# aq_mx_v1-6-0b.net
KiCad netlist of a schematic drawn in EAGLE
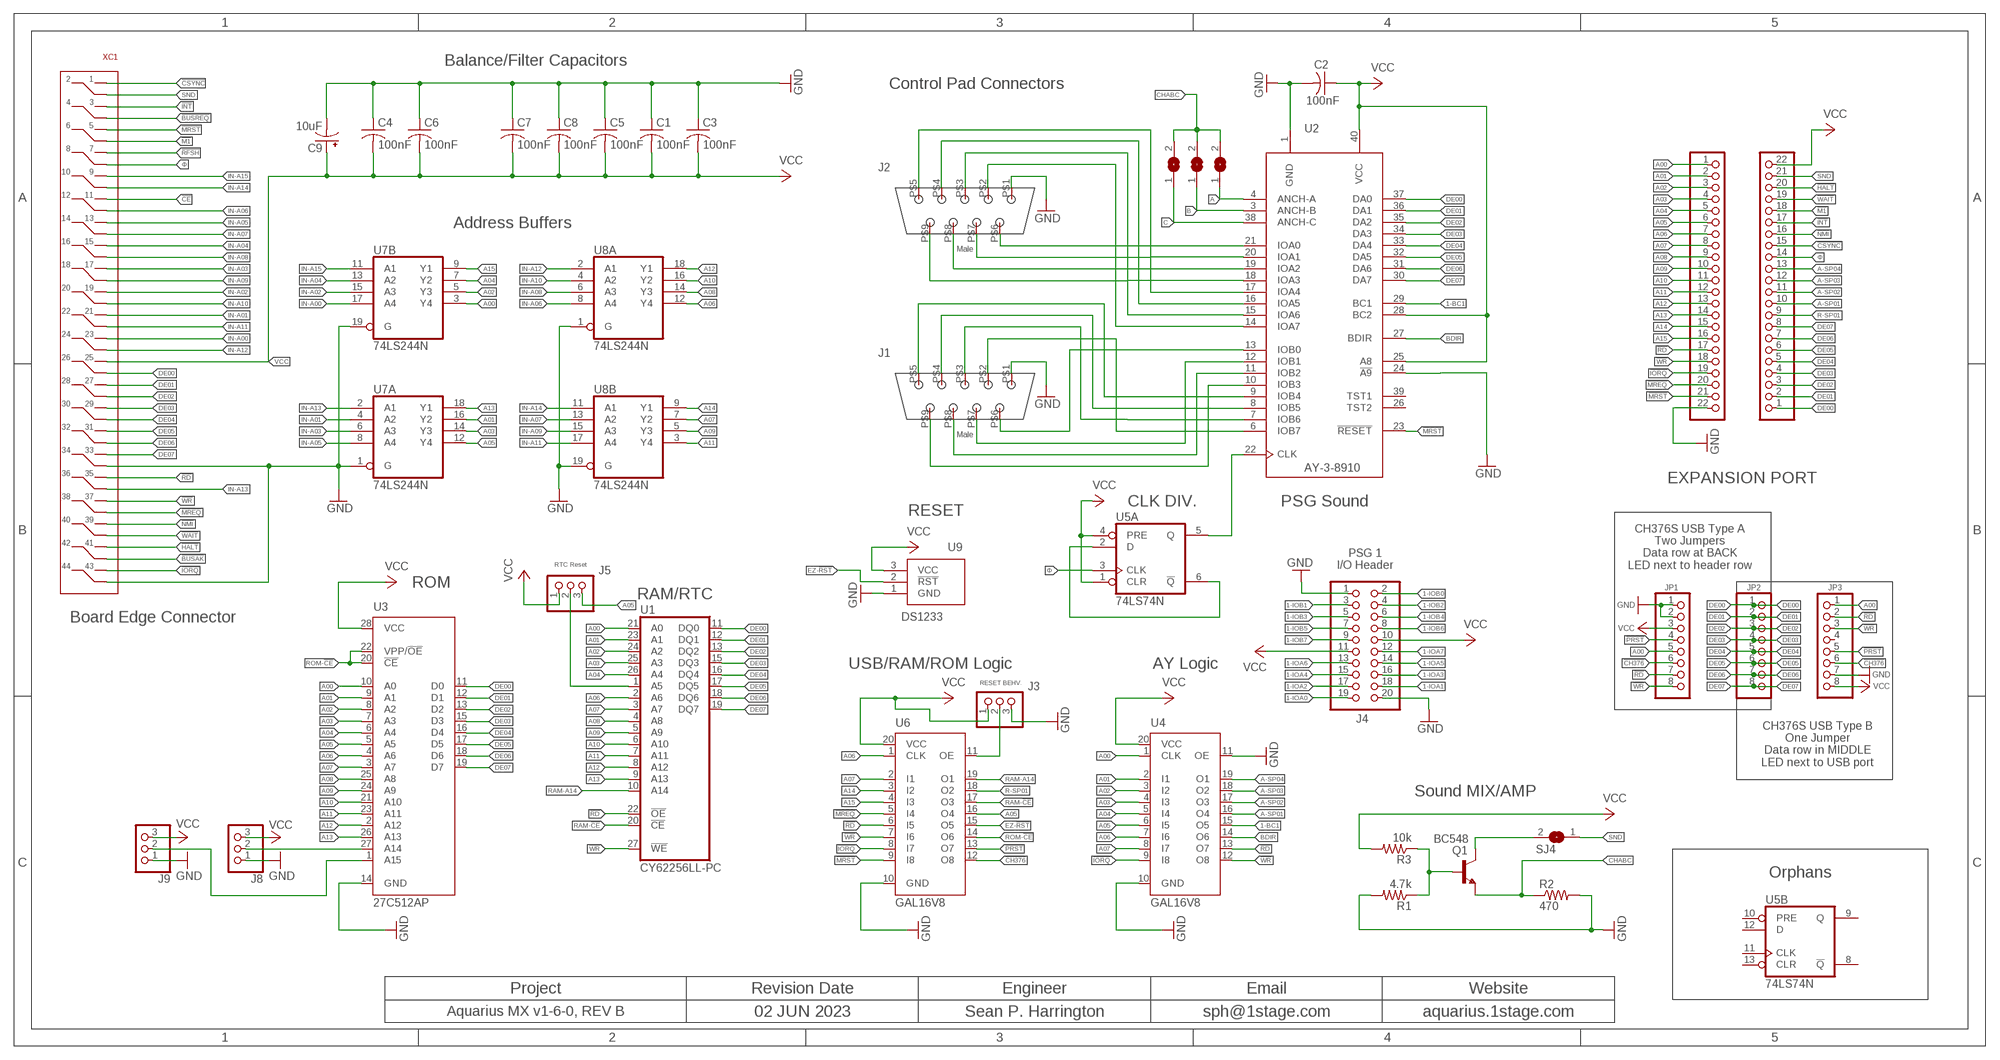
[diagram p0: schematic, sheet 1]

(export (version "E")
  (design (tool "Eeschema 10.0.6"))
  (components
    (comp (ref "C1")
      (value "100nF")
      (footprint "eagle-import:C050-025X075")
      (libsource (lib "eagle-import") (part "C-US050-025X075"))
    )
    (comp (ref "C2")
      (value "100nF")
      (footprint "eagle-import:C050-025X075")
      (libsource (lib "eagle-import") (part "C-US050-025X075"))
    )
    (comp (ref "C3")
      (value "100nF")
      (footprint "eagle-import:C050-025X075")
      (libsource (lib "eagle-import") (part "C-US050-025X075"))
    )
    (comp (ref "C4")
      (value "100nF")
      (footprint "eagle-import:C050-025X075")
      (libsource (lib "eagle-import") (part "C-US050-025X075"))
    )
    (comp (ref "C5")
      (value "100nF")
      (footprint "eagle-import:C050-025X075")
      (libsource (lib "eagle-import") (part "C-US050-025X075"))
    )
    (comp (ref "C6")
      (value "100nF")
      (footprint "eagle-import:C050-025X075")
      (libsource (lib "eagle-import") (part "C-US050-025X075"))
    )
    (comp (ref "C7")
      (value "100nF")
      (footprint "eagle-import:C050-025X075")
      (libsource (lib "eagle-import") (part "C-US050-025X075"))
    )
    (comp (ref "C8")
      (value "100nF")
      (footprint "eagle-import:C050-025X075")
      (libsource (lib "eagle-import") (part "C-US050-025X075"))
    )
    (comp (ref "C9")
      (value "10uF")
      (footprint "eagle-import:E22-6")
      (libsource (lib "eagle-import") (part "CPOL-USE22-6AXIAL"))
    )
    (comp (ref "J1")
      (value "DB9-MALE-RA")
      (footprint "eagle-import:DB9-MALE-RA")
      (libsource (lib "eagle-import") (part "DB9-MALE-RA"))
    )
    (comp (ref "J2")
      (value "DB9-MALE-RA")
      (footprint "eagle-import:DB9-MALE-RA")
      (libsource (lib "eagle-import") (part "DB9-MALE-RA"))
    )
    (comp (ref "J3")
      (value "RESET BEHV.")
      (footprint "eagle-import:1X03")
      (libsource (lib "eagle-import") (part "PINHD-1X3"))
    )
    (comp (ref "J4")
      (value "PINHD-2X10")
      (footprint "eagle-import:2X10")
      (libsource (lib "eagle-import") (part "PINHD-2X10"))
    )
    (comp (ref "J5")
      (value "RTC Reset")
      (footprint "eagle-import:1X03")
      (libsource (lib "eagle-import") (part "PINHD-1X3"))
    )
    (comp (ref "J6")
      (value "PINHD-1X22")
      (footprint "eagle-import:1X22")
      (libsource (lib "eagle-import") (part "PINHD-1X22"))
    )
    (comp (ref "J7")
      (value "PINHD-1X22")
      (footprint "eagle-import:1X22")
      (libsource (lib "eagle-import") (part "PINHD-1X22"))
    )
    (comp (ref "J8")
      (value "PINHD-1X3")
      (footprint "eagle-import:1X03")
      (libsource (lib "eagle-import") (part "PINHD-1X3"))
    )
    (comp (ref "J9")
      (value "PINHD-1X3")
      (footprint "eagle-import:1X03")
      (libsource (lib "eagle-import") (part "PINHD-1X3"))
    )
    (comp (ref "JP1")
      (value "PINHD-1X8")
      (footprint "eagle-import:1X08")
      (libsource (lib "eagle-import") (part "PINHD-1X8"))
    )
    (comp (ref "JP2")
      (value "PINHD-1X8")
      (footprint "eagle-import:1X08")
      (libsource (lib "eagle-import") (part "PINHD-1X8"))
    )
    (comp (ref "JP3")
      (value "PINHD-1X8")
      (footprint "eagle-import:1X08")
      (libsource (lib "eagle-import") (part "PINHD-1X8"))
    )
    (comp (ref "Q1")
      (value "BC548")
      (footprint "eagle-import:TO92-CBE")
      (libsource (lib "eagle-import") (part "-NPN-TO92-CBEBC548"))
    )
    (comp (ref "R1")
      (value "4.7k")
      (footprint "eagle-import:0204_7")
      (libsource (lib "eagle-import") (part "R-US_0204/7"))
    )
    (comp (ref "R2")
      (value "470")
      (footprint "eagle-import:0204_7")
      (libsource (lib "eagle-import") (part "R-US_0204/7"))
    )
    (comp (ref "R3")
      (value "10k")
      (footprint "eagle-import:0204_7")
      (libsource (lib "eagle-import") (part "R-US_0204/7"))
    )
    (comp (ref "SJ1") (value "SJ") (footprint "eagle-import:SJ") (libsource (lib "eagle-import") (part "SJ")))
    (comp (ref "SJ2") (value "SJ") (footprint "eagle-import:SJ") (libsource (lib "eagle-import") (part "SJ")))
    (comp (ref "SJ3") (value "SJ") (footprint "eagle-import:SJ") (libsource (lib "eagle-import") (part "SJ")))
    (comp (ref "SJ4") (value "SJ") (footprint "eagle-import:SJ") (libsource (lib "eagle-import") (part "SJ")))
    (comp (ref "U1")
      (value "CY62256LL-PC")
      (footprint "eagle-import:DIL28-6")
      (libsource (lib "eagle-import") (part "CY62256LL-?PC"))
    )
    (comp (ref "U2")
      (value "AY-3-8910")
      (footprint "eagle-import:RAD38910-DIL40-6")
      (libsource (lib "eagle-import") (part "RAD38910DIL40-6"))
    )
    (comp (ref "U3")
      (value "27C512AP")
      (footprint "eagle-import:DIL28-6")
      (fields (field (name "MPN") "M27C512-90B6"))
      (libsource (lib "eagle-import") (part "27512APC"))
    )
    (comp (ref "U4")
      (value "GAL16V8")
      (footprint "eagle-import:DIL20")
      (fields (field (name "MPN") "ATF16V8CZ-15PU"))
      (libsource (lib "eagle-import") (part "ATF16V8BP3"))
    )
    (comp (ref "U5")
      (value "74LS74N")
      (footprint "eagle-import:DIL14")
      (libsource (lib "eagle-import") (part "7474NLS"))
    )
    (comp (ref "U6")
      (value "GAL16V8")
      (footprint "eagle-import:DIL20")
      (fields (field (name "MPN") "ATF16V8CZ-15PU"))
      (libsource (lib "eagle-import") (part "ATF16V8BP3"))
    )
    (comp (ref "U7")
      (value "74LS244N")
      (footprint "eagle-import:DIL20")
      (libsource (lib "eagle-import") (part "74244NLS"))
    )
    (comp (ref "U8")
      (value "74LS244N")
      (footprint "eagle-import:DIL20")
      (libsource (lib "eagle-import") (part "74244NLS"))
    )
    (comp (ref "U9")
      (value "DS1233")
      (footprint "eagle-import:TO-92")
      (fields
        (field (name "ARROW_PART_NUMBER") "DS1233-10+")
        (field (name "MOUSER_PART_NUMBER") "700-DS1233-10")
      )
      (libsource (lib "eagle-import") (part "DS1233-10+"))
    )
    (comp (ref "XC1")
      (value "AQ-CART-EDGE")
      (footprint "eagle-import:AQ-CART-EDGE")
      (libsource (lib "eagle-import") (part "AQ-CART-EDGE"))
    )
  )
  (nets
    (net (code "1") (name "/EZ-~{RST}") (class "Default")
      (node (ref "U6") (pin "15") (pinfunction "O5_15") (pintype "output"))
      (node (ref "U9") (pin "2") (pinfunction "~{RST}_2") (pintype "input"))
    )
    (net (code "2") (name "/RAM-~{CE}") (class "Default")
      (node (ref "U1") (pin "20") (pinfunction "~{CE}_20") (pintype "input"))
      (node (ref "U6") (pin "17") (pinfunction "O3_17") (pintype "output"))
    )
    (net (code "3") (name "/ROM-~{CE}") (class "Default")
      (node (ref "U3") (pin "20") (pinfunction "~{CE}_20") (pintype "input"))
      (node (ref "U3") (pin "22") (pinfunction "VPP/~{OE}_22") (pintype "input"))
      (node (ref "U6") (pin "14") (pinfunction "O6_14") (pintype "output"))
    )
    (net (code "4") (name "/~{BUSAK}") (class "Default")
      (node (ref "XC1") (pin "P$42") (pinfunction "X42_P$42") (pintype "bidirectional"))
    )
    (net (code "5") (name "/~{BUSREQ}") (class "Default")
      (node (ref "XC1") (pin "P$4") (pinfunction "X4_P$4") (pintype "bidirectional"))
    )
    (net (code "6") (name "/~{CE}") (class "Default")
      (node (ref "XC1") (pin "P$11") (pinfunction "X11_P$11") (pintype "bidirectional"))
    )
    (net (code "7") (name "/~{CH376}") (class "Default")
      (node (ref "JP1") (pin "6") (pinfunction "6_6") (pintype "passive"))
      (node (ref "JP3") (pin "6") (pinfunction "6_6") (pintype "passive"))
      (node (ref "U6") (pin "12") (pinfunction "O8_12") (pintype "output"))
    )
    (net (code "8") (name "/~{CSYNC}") (class "Default")
      (node (ref "J6") (pin "15") (pinfunction "15_15") (pintype "passive"))
      (node (ref "XC1") (pin "P$1") (pinfunction "X1_P$1") (pintype "bidirectional"))
    )
    (net (code "9") (name "/~{HALT}") (class "Default")
      (node (ref "J6") (pin "20") (pinfunction "20_20") (pintype "passive"))
      (node (ref "XC1") (pin "P$41") (pinfunction "X41_P$41") (pintype "bidirectional"))
    )
    (net (code "10") (name "/~{INT}") (class "Default")
      (node (ref "J6") (pin "17") (pinfunction "17_17") (pintype "passive"))
      (node (ref "XC1") (pin "P$3") (pinfunction "X3_P$3") (pintype "bidirectional"))
    )
    (net (code "11") (name "/~{IORQ}") (class "Default")
      (node (ref "J7") (pin "19") (pinfunction "19_19") (pintype "passive"))
      (node (ref "U4") (pin "9") (pinfunction "I8_9") (pintype "input"))
      (node (ref "U6") (pin "8") (pinfunction "I7_8") (pintype "input"))
      (node (ref "XC1") (pin "P$43") (pinfunction "X43_P$43") (pintype "bidirectional"))
    )
    (net (code "12") (name "/~{M1}") (class "Default")
      (node (ref "J6") (pin "18") (pinfunction "18_18") (pintype "passive"))
      (node (ref "XC1") (pin "P$6") (pinfunction "X6_P$6") (pintype "bidirectional"))
    )
    (net (code "13") (name "/~{MREQ}") (class "Default")
      (node (ref "J7") (pin "20") (pinfunction "20_20") (pintype "passive"))
      (node (ref "U6") (pin "5") (pinfunction "I4_5") (pintype "input"))
      (node (ref "XC1") (pin "P$38") (pinfunction "X38_P$38") (pintype "bidirectional"))
    )
    (net (code "14") (name "/~{MRST}") (class "Default")
      (node (ref "J7") (pin "21") (pinfunction "21_21") (pintype "passive"))
      (node (ref "U2") (pin "23") (pinfunction "~{RESET}_23") (pintype "bidirectional"))
      (node (ref "U6") (pin "9") (pinfunction "I8_9") (pintype "input"))
      (node (ref "XC1") (pin "P$5") (pinfunction "X5_P$5") (pintype "bidirectional"))
    )
    (net (code "15") (name "/~{NMI}") (class "Default")
      (node (ref "J6") (pin "16") (pinfunction "16_16") (pintype "passive"))
      (node (ref "XC1") (pin "P$39") (pinfunction "X39_P$39") (pintype "bidirectional"))
    )
    (net (code "16") (name "/~{PRST}") (class "Default")
      (node (ref "JP1") (pin "4") (pinfunction "4_4") (pintype "passive"))
      (node (ref "JP3") (pin "5") (pinfunction "5_5") (pintype "passive"))
      (node (ref "U6") (pin "13") (pinfunction "O7_13") (pintype "output"))
    )
    (net (code "17") (name "/~{RD}") (class "Default")
      (node (ref "J7") (pin "17") (pinfunction "17_17") (pintype "passive"))
      (node (ref "JP1") (pin "7") (pinfunction "7_7") (pintype "passive"))
      (node (ref "JP3") (pin "2") (pinfunction "2_2") (pintype "passive"))
      (node (ref "U1") (pin "22") (pinfunction "~{OE}_22") (pintype "input"))
      (node (ref "U4") (pin "13") (pinfunction "O7_13") (pintype "output"))
      (node (ref "U6") (pin "6") (pinfunction "I5_6") (pintype "input"))
      (node (ref "XC1") (pin "P$35") (pinfunction "X35_P$35") (pintype "bidirectional"))
    )
    (net (code "18") (name "/~{RFSH}") (class "Default")
      (node (ref "XC1") (pin "P$7") (pinfunction "X7_P$7") (pintype "bidirectional"))
    )
    (net (code "19") (name "/~{WAIT}") (class "Default")
      (node (ref "J6") (pin "19") (pinfunction "19_19") (pintype "passive"))
      (node (ref "XC1") (pin "P$40") (pinfunction "X40_P$40") (pintype "bidirectional"))
    )
    (net (code "20") (name "/~{WR}") (class "Default")
      (node (ref "J7") (pin "18") (pinfunction "18_18") (pintype "passive"))
      (node (ref "JP1") (pin "8") (pinfunction "8_8") (pintype "passive"))
      (node (ref "JP3") (pin "3") (pinfunction "3_3") (pintype "passive"))
      (node (ref "U1") (pin "27") (pinfunction "~{WE}_27") (pintype "input"))
      (node (ref "U4") (pin "12") (pinfunction "O8_12") (pintype "output"))
      (node (ref "U6") (pin "7") (pinfunction "I6_7") (pintype "input"))
      (node (ref "XC1") (pin "P$37") (pinfunction "X37_P$37") (pintype "bidirectional"))
    )
    (net (code "21") (name "1-BC1") (class "Default")
      (node (ref "U2") (pin "29") (pinfunction "BC1_29") (pintype "bidirectional"))
      (node (ref "U4") (pin "15") (pinfunction "O5_15") (pintype "output"))
    )
    (net (code "22") (name "1-IOA0") (class "Default")
      (node (ref "J2") (pin "P$6") (pinfunction "P$6_P$6") (pintype "bidirectional"))
      (node (ref "J4") (pin "19") (pinfunction "19_19") (pintype "passive"))
      (node (ref "U2") (pin "21") (pinfunction "IOA0_21") (pintype "bidirectional"))
    )
    (net (code "23") (name "1-IOA1") (class "Default")
      (node (ref "J2") (pin "P$7") (pinfunction "P$7_P$7") (pintype "bidirectional"))
      (node (ref "J4") (pin "18") (pinfunction "18_18") (pintype "passive"))
      (node (ref "U2") (pin "20") (pinfunction "IOA1_20") (pintype "bidirectional"))
    )
    (net (code "24") (name "1-IOA2") (class "Default")
      (node (ref "J2") (pin "P$8") (pinfunction "P$8_P$8") (pintype "bidirectional"))
      (node (ref "J4") (pin "17") (pinfunction "17_17") (pintype "passive"))
      (node (ref "U2") (pin "19") (pinfunction "IOA2_19") (pintype "bidirectional"))
    )
    (net (code "25") (name "1-IOA3") (class "Default")
      (node (ref "J2") (pin "P$9") (pinfunction "P$9_P$9") (pintype "bidirectional"))
      (node (ref "J4") (pin "16") (pinfunction "16_16") (pintype "passive"))
      (node (ref "U2") (pin "18") (pinfunction "IOA3_18") (pintype "bidirectional"))
    )
    (net (code "26") (name "1-IOA4") (class "Default")
      (node (ref "J2") (pin "P$5") (pinfunction "P$5_P$5") (pintype "bidirectional"))
      (node (ref "J4") (pin "15") (pinfunction "15_15") (pintype "passive"))
      (node (ref "U2") (pin "17") (pinfunction "IOA4_17") (pintype "bidirectional"))
    )
    (net (code "27") (name "1-IOA5") (class "Default")
      (node (ref "J2") (pin "P$4") (pinfunction "P$4_P$4") (pintype "bidirectional"))
      (node (ref "J4") (pin "14") (pinfunction "14_14") (pintype "passive"))
      (node (ref "U2") (pin "16") (pinfunction "IOA5_16") (pintype "bidirectional"))
    )
    (net (code "28") (name "1-IOA6") (class "Default")
      (node (ref "J2") (pin "P$3") (pinfunction "P$3_P$3") (pintype "bidirectional"))
      (node (ref "J4") (pin "13") (pinfunction "13_13") (pintype "passive"))
      (node (ref "U2") (pin "15") (pinfunction "IOA6_15") (pintype "bidirectional"))
    )
    (net (code "29") (name "1-IOA7") (class "Default")
      (node (ref "J2") (pin "P$2") (pinfunction "P$2_P$2") (pintype "bidirectional"))
      (node (ref "J4") (pin "12") (pinfunction "12_12") (pintype "passive"))
      (node (ref "U2") (pin "14") (pinfunction "IOA7_14") (pintype "bidirectional"))
    )
    (net (code "30") (name "1-IOB0") (class "Default")
      (node (ref "J1") (pin "P$6") (pinfunction "P$6_P$6") (pintype "bidirectional"))
      (node (ref "J4") (pin "2") (pinfunction "2_2") (pintype "passive"))
      (node (ref "U2") (pin "13") (pinfunction "IOB0_13") (pintype "bidirectional"))
    )
    (net (code "31") (name "1-IOB1") (class "Default")
      (node (ref "J1") (pin "P$7") (pinfunction "P$7_P$7") (pintype "bidirectional"))
      (node (ref "J4") (pin "3") (pinfunction "3_3") (pintype "passive"))
      (node (ref "U2") (pin "12") (pinfunction "IOB1_12") (pintype "bidirectional"))
    )
    (net (code "32") (name "1-IOB2") (class "Default")
      (node (ref "J1") (pin "P$8") (pinfunction "P$8_P$8") (pintype "bidirectional"))
      (node (ref "J4") (pin "4") (pinfunction "4_4") (pintype "passive"))
      (node (ref "U2") (pin "11") (pinfunction "IOB2_11") (pintype "bidirectional"))
    )
    (net (code "33") (name "1-IOB3") (class "Default")
      (node (ref "J1") (pin "P$9") (pinfunction "P$9_P$9") (pintype "bidirectional"))
      (node (ref "J4") (pin "5") (pinfunction "5_5") (pintype "passive"))
      (node (ref "U2") (pin "10") (pinfunction "IOB3_10") (pintype "bidirectional"))
    )
    (net (code "34") (name "1-IOB4") (class "Default")
      (node (ref "J1") (pin "P$5") (pinfunction "P$5_P$5") (pintype "bidirectional"))
      (node (ref "J4") (pin "6") (pinfunction "6_6") (pintype "passive"))
      (node (ref "U2") (pin "9") (pinfunction "IOB4_9") (pintype "bidirectional"))
    )
    (net (code "35") (name "1-IOB5") (class "Default")
      (node (ref "J1") (pin "P$4") (pinfunction "P$4_P$4") (pintype "bidirectional"))
      (node (ref "J4") (pin "7") (pinfunction "7_7") (pintype "passive"))
      (node (ref "U2") (pin "8") (pinfunction "IOB5_8") (pintype "bidirectional"))
    )
    (net (code "36") (name "1-IOB6") (class "Default")
      (node (ref "J1") (pin "P$3") (pinfunction "P$3_P$3") (pintype "bidirectional"))
      (node (ref "J4") (pin "8") (pinfunction "8_8") (pintype "passive"))
      (node (ref "U2") (pin "7") (pinfunction "IOB6_7") (pintype "bidirectional"))
    )
    (net (code "37") (name "1-IOB7") (class "Default")
      (node (ref "J1") (pin "P$2") (pinfunction "P$2_P$2") (pintype "bidirectional"))
      (node (ref "J4") (pin "9") (pinfunction "9_9") (pintype "passive"))
      (node (ref "U2") (pin "6") (pinfunction "IOB7_6") (pintype "bidirectional"))
    )
    (net (code "38") (name "A") (class "Default")
      (node (ref "SJ1") (pin "1") (pinfunction "1_1") (pintype "passive"))
      (node (ref "U2") (pin "4") (pinfunction "ANCH-A_4") (pintype "bidirectional"))
    )
    (net (code "39") (name "A-SP01") (class "Default")
      (node (ref "J6") (pin "10") (pinfunction "10_10") (pintype "passive"))
      (node (ref "U4") (pin "16") (pinfunction "O4_16") (pintype "output"))
    )
    (net (code "40") (name "A-SP02") (class "Default")
      (node (ref "J6") (pin "11") (pinfunction "11_11") (pintype "passive"))
      (node (ref "U4") (pin "17") (pinfunction "O3_17") (pintype "output"))
    )
    (net (code "41") (name "A-SP03") (class "Default")
      (node (ref "J6") (pin "12") (pinfunction "12_12") (pintype "passive"))
      (node (ref "U4") (pin "18") (pinfunction "O2_18") (pintype "output"))
    )
    (net (code "42") (name "A-SP04") (class "Default")
      (node (ref "J6") (pin "13") (pinfunction "13_13") (pintype "passive"))
      (node (ref "U4") (pin "19") (pinfunction "O1_19") (pintype "output"))
    )
    (net (code "43") (name "A00") (class "Default")
      (node (ref "J7") (pin "1") (pinfunction "1_1") (pintype "passive"))
      (node (ref "JP1") (pin "5") (pinfunction "5_5") (pintype "passive"))
      (node (ref "JP3") (pin "1") (pinfunction "1_1") (pintype "passive"))
      (node (ref "U1") (pin "21") (pinfunction "A0_21") (pintype "input"))
      (node (ref "U3") (pin "10") (pinfunction "A0_10") (pintype "input"))
      (node (ref "U4") (pin "1") (pinfunction "CLK_1") (pintype "input"))
      (node (ref "U7") (pin "3") (pinfunction "Y4_3") (pintype "tri_state"))
    )
    (net (code "44") (name "A01") (class "Default")
      (node (ref "J7") (pin "2") (pinfunction "2_2") (pintype "passive"))
      (node (ref "U1") (pin "23") (pinfunction "A1_23") (pintype "input"))
      (node (ref "U3") (pin "9") (pinfunction "A1_9") (pintype "input"))
      (node (ref "U4") (pin "2") (pinfunction "I1_2") (pintype "input"))
      (node (ref "U7") (pin "16") (pinfunction "Y2_16") (pintype "tri_state"))
    )
    (net (code "45") (name "A02") (class "Default")
      (node (ref "J7") (pin "3") (pinfunction "3_3") (pintype "passive"))
      (node (ref "U1") (pin "24") (pinfunction "A2_24") (pintype "input"))
      (node (ref "U3") (pin "8") (pinfunction "A2_8") (pintype "input"))
      (node (ref "U4") (pin "3") (pinfunction "I2_3") (pintype "input"))
      (node (ref "U7") (pin "5") (pinfunction "Y3_5") (pintype "tri_state"))
    )
    (net (code "46") (name "A03") (class "Default")
      (node (ref "J7") (pin "4") (pinfunction "4_4") (pintype "passive"))
      (node (ref "U1") (pin "25") (pinfunction "A3_25") (pintype "input"))
      (node (ref "U3") (pin "7") (pinfunction "A3_7") (pintype "input"))
      (node (ref "U4") (pin "4") (pinfunction "I3_4") (pintype "input"))
      (node (ref "U7") (pin "14") (pinfunction "Y3_14") (pintype "tri_state"))
    )
    (net (code "47") (name "A04") (class "Default")
      (node (ref "J7") (pin "5") (pinfunction "5_5") (pintype "passive"))
      (node (ref "U1") (pin "26") (pinfunction "A4_26") (pintype "input"))
      (node (ref "U3") (pin "6") (pinfunction "A4_6") (pintype "input"))
      (node (ref "U4") (pin "5") (pinfunction "I4_5") (pintype "input"))
      (node (ref "U7") (pin "7") (pinfunction "Y2_7") (pintype "tri_state"))
    )
    (net (code "48") (name "A05") (class "Default")
      (node (ref "J5") (pin "3") (pinfunction "3_3") (pintype "passive"))
      (node (ref "J7") (pin "6") (pinfunction "6_6") (pintype "passive"))
      (node (ref "U3") (pin "5") (pinfunction "A5_5") (pintype "input"))
      (node (ref "U4") (pin "6") (pinfunction "I5_6") (pintype "input"))
      (node (ref "U6") (pin "16") (pinfunction "O4_16") (pintype "output"))
      (node (ref "U7") (pin "12") (pinfunction "Y4_12") (pintype "tri_state"))
    )
    (net (code "49") (name "A06") (class "Default")
      (node (ref "J7") (pin "7") (pinfunction "7_7") (pintype "passive"))
      (node (ref "U1") (pin "2") (pinfunction "A6_2") (pintype "input"))
      (node (ref "U3") (pin "4") (pinfunction "A6_4") (pintype "input"))
      (node (ref "U4") (pin "7") (pinfunction "I6_7") (pintype "input"))
      (node (ref "U6") (pin "1") (pinfunction "CLK_1") (pintype "input"))
      (node (ref "U8") (pin "12") (pinfunction "Y4_12") (pintype "tri_state"))
    )
    (net (code "50") (name "A07") (class "Default")
      (node (ref "J7") (pin "8") (pinfunction "8_8") (pintype "passive"))
      (node (ref "U1") (pin "3") (pinfunction "A7_3") (pintype "input"))
      (node (ref "U3") (pin "3") (pinfunction "A7_3") (pintype "input"))
      (node (ref "U4") (pin "8") (pinfunction "I7_8") (pintype "input"))
      (node (ref "U6") (pin "2") (pinfunction "I1_2") (pintype "input"))
      (node (ref "U8") (pin "7") (pinfunction "Y2_7") (pintype "tri_state"))
    )
    (net (code "51") (name "A08") (class "Default")
      (node (ref "J7") (pin "9") (pinfunction "9_9") (pintype "passive"))
      (node (ref "U1") (pin "4") (pinfunction "A8_4") (pintype "input"))
      (node (ref "U3") (pin "25") (pinfunction "A8_25") (pintype "input"))
      (node (ref "U8") (pin "14") (pinfunction "Y3_14") (pintype "tri_state"))
    )
    (net (code "52") (name "A09") (class "Default")
      (node (ref "J7") (pin "10") (pinfunction "10_10") (pintype "passive"))
      (node (ref "U1") (pin "5") (pinfunction "A9_5") (pintype "input"))
      (node (ref "U3") (pin "24") (pinfunction "A9_24") (pintype "input"))
      (node (ref "U8") (pin "5") (pinfunction "Y3_5") (pintype "tri_state"))
    )
    (net (code "53") (name "A10") (class "Default")
      (node (ref "J7") (pin "11") (pinfunction "11_11") (pintype "passive"))
      (node (ref "U1") (pin "6") (pinfunction "A10_6") (pintype "input"))
      (node (ref "U3") (pin "21") (pinfunction "A10_21") (pintype "input"))
      (node (ref "U8") (pin "16") (pinfunction "Y2_16") (pintype "tri_state"))
    )
    (net (code "54") (name "A11") (class "Default")
      (node (ref "J7") (pin "12") (pinfunction "12_12") (pintype "passive"))
      (node (ref "U1") (pin "7") (pinfunction "A11_7") (pintype "input"))
      (node (ref "U3") (pin "23") (pinfunction "A11_23") (pintype "input"))
      (node (ref "U8") (pin "3") (pinfunction "Y4_3") (pintype "tri_state"))
    )
    (net (code "55") (name "A12") (class "Default")
      (node (ref "J7") (pin "13") (pinfunction "13_13") (pintype "passive"))
      (node (ref "U1") (pin "8") (pinfunction "A12_8") (pintype "input"))
      (node (ref "U3") (pin "2") (pinfunction "A12_2") (pintype "input"))
      (node (ref "U8") (pin "18") (pinfunction "Y1_18") (pintype "tri_state"))
    )
    (net (code "56") (name "A13") (class "Default")
      (node (ref "J7") (pin "14") (pinfunction "14_14") (pintype "passive"))
      (node (ref "U1") (pin "9") (pinfunction "A13_9") (pintype "input"))
      (node (ref "U3") (pin "26") (pinfunction "A13_26") (pintype "input"))
      (node (ref "U7") (pin "18") (pinfunction "Y1_18") (pintype "tri_state"))
    )
    (net (code "57") (name "A14") (class "Default")
      (node (ref "J7") (pin "15") (pinfunction "15_15") (pintype "passive"))
      (node (ref "U6") (pin "3") (pinfunction "I2_3") (pintype "input"))
      (node (ref "U8") (pin "9") (pinfunction "Y1_9") (pintype "tri_state"))
    )
    (net (code "58") (name "A15") (class "Default")
      (node (ref "J7") (pin "16") (pinfunction "16_16") (pintype "passive"))
      (node (ref "U6") (pin "4") (pinfunction "I3_4") (pintype "input"))
      (node (ref "U7") (pin "9") (pinfunction "Y1_9") (pintype "tri_state"))
    )
    (net (code "59") (name "B") (class "Default")
      (node (ref "SJ2") (pin "1") (pinfunction "1_1") (pintype "passive"))
      (node (ref "U2") (pin "3") (pinfunction "ANCH-B_3") (pintype "bidirectional"))
    )
    (net (code "60") (name "BDIR") (class "Default")
      (node (ref "U2") (pin "27") (pinfunction "BDIR_27") (pintype "bidirectional"))
      (node (ref "U4") (pin "14") (pinfunction "O6_14") (pintype "output"))
    )
    (net (code "61") (name "C") (class "Default")
      (node (ref "SJ3") (pin "1") (pinfunction "1_1") (pintype "passive"))
      (node (ref "U2") (pin "38") (pinfunction "ANCH-C_38") (pintype "bidirectional"))
    )
    (net (code "62") (name "CHABC") (class "Default")
      (node (ref "Q1") (pin "E") (pinfunction "E_E") (pintype "passive"))
      (node (ref "R2") (pin "1") (pinfunction "1_1") (pintype "passive"))
      (node (ref "SJ1") (pin "2") (pinfunction "2_2") (pintype "passive"))
      (node (ref "SJ2") (pin "2") (pinfunction "2_2") (pintype "passive"))
      (node (ref "SJ3") (pin "2") (pinfunction "2_2") (pintype "passive"))
    )
    (net (code "63") (name "DE00") (class "Default")
      (node (ref "J6") (pin "1") (pinfunction "1_1") (pintype "passive"))
      (node (ref "JP2") (pin "1") (pinfunction "1_1") (pintype "passive"))
      (node (ref "U1") (pin "11") (pinfunction "DQ0_11") (pintype "bidirectional"))
      (node (ref "U2") (pin "37") (pinfunction "DA0_37") (pintype "bidirectional"))
      (node (ref "U3") (pin "11") (pinfunction "D0_11") (pintype "tri_state"))
      (node (ref "XC1") (pin "P$26") (pinfunction "X26_P$26") (pintype "bidirectional"))
    )
    (net (code "64") (name "DE01") (class "Default")
      (node (ref "J6") (pin "2") (pinfunction "2_2") (pintype "passive"))
      (node (ref "JP2") (pin "2") (pinfunction "2_2") (pintype "passive"))
      (node (ref "U1") (pin "12") (pinfunction "DQ1_12") (pintype "bidirectional"))
      (node (ref "U2") (pin "36") (pinfunction "DA1_36") (pintype "bidirectional"))
      (node (ref "U3") (pin "12") (pinfunction "D1_12") (pintype "tri_state"))
      (node (ref "XC1") (pin "P$27") (pinfunction "X27_P$27") (pintype "bidirectional"))
    )
    (net (code "65") (name "DE02") (class "Default")
      (node (ref "J6") (pin "3") (pinfunction "3_3") (pintype "passive"))
      (node (ref "JP2") (pin "3") (pinfunction "3_3") (pintype "passive"))
      (node (ref "U1") (pin "13") (pinfunction "DQ2_13") (pintype "bidirectional"))
      (node (ref "U2") (pin "35") (pinfunction "DA2_35") (pintype "bidirectional"))
      (node (ref "U3") (pin "13") (pinfunction "D2_13") (pintype "tri_state"))
      (node (ref "XC1") (pin "P$28") (pinfunction "X28_P$28") (pintype "bidirectional"))
    )
    (net (code "66") (name "DE03") (class "Default")
      (node (ref "J6") (pin "4") (pinfunction "4_4") (pintype "passive"))
      (node (ref "JP2") (pin "4") (pinfunction "4_4") (pintype "passive"))
      (node (ref "U1") (pin "15") (pinfunction "DQ3_15") (pintype "bidirectional"))
      (node (ref "U2") (pin "34") (pinfunction "DA3_34") (pintype "bidirectional"))
      (node (ref "U3") (pin "15") (pinfunction "D3_15") (pintype "tri_state"))
      (node (ref "XC1") (pin "P$29") (pinfunction "X29_P$29") (pintype "bidirectional"))
    )
    (net (code "67") (name "DE04") (class "Default")
      (node (ref "J6") (pin "5") (pinfunction "5_5") (pintype "passive"))
      (node (ref "JP2") (pin "5") (pinfunction "5_5") (pintype "passive"))
      (node (ref "U1") (pin "16") (pinfunction "DQ4_16") (pintype "bidirectional"))
      (node (ref "U2") (pin "33") (pinfunction "DA4_33") (pintype "bidirectional"))
      (node (ref "U3") (pin "16") (pinfunction "D4_16") (pintype "tri_state"))
      (node (ref "XC1") (pin "P$30") (pinfunction "X30_P$30") (pintype "bidirectional"))
    )
    (net (code "68") (name "DE05") (class "Default")
      (node (ref "J6") (pin "6") (pinfunction "6_6") (pintype "passive"))
      (node (ref "JP2") (pin "6") (pinfunction "6_6") (pintype "passive"))
      (node (ref "U1") (pin "17") (pinfunction "DQ5_17") (pintype "bidirectional"))
      (node (ref "U2") (pin "32") (pinfunction "DA5_32") (pintype "bidirectional"))
      (node (ref "U3") (pin "17") (pinfunction "D5_17") (pintype "tri_state"))
      (node (ref "XC1") (pin "P$31") (pinfunction "X31_P$31") (pintype "bidirectional"))
    )
    (net (code "69") (name "DE06") (class "Default")
      (node (ref "J6") (pin "7") (pinfunction "7_7") (pintype "passive"))
      (node (ref "JP2") (pin "7") (pinfunction "7_7") (pintype "passive"))
      (node (ref "U1") (pin "18") (pinfunction "DQ6_18") (pintype "bidirectional"))
      (node (ref "U2") (pin "31") (pinfunction "DA6_31") (pintype "bidirectional"))
      (node (ref "U3") (pin "18") (pinfunction "D6_18") (pintype "tri_state"))
      (node (ref "XC1") (pin "P$32") (pinfunction "X32_P$32") (pintype "bidirectional"))
    )
    (net (code "70") (name "DE07") (class "Default")
      (node (ref "J6") (pin "8") (pinfunction "8_8") (pintype "passive"))
      (node (ref "JP2") (pin "8") (pinfunction "8_8") (pintype "passive"))
      (node (ref "U1") (pin "19") (pinfunction "DQ7_19") (pintype "bidirectional"))
      (node (ref "U2") (pin "30") (pinfunction "DA7_30") (pintype "bidirectional"))
      (node (ref "U3") (pin "19") (pinfunction "D7_19") (pintype "tri_state"))
      (node (ref "XC1") (pin "P$33") (pinfunction "X33_P$33") (pintype "bidirectional"))
    )
    (net (code "71") (name "GND") (class "Default")
      (node (ref "C1") (pin "1") (pinfunction "1_1") (pintype "passive"))
      (node (ref "C2") (pin "2") (pinfunction "2_2") (pintype "passive"))
      (node (ref "C3") (pin "1") (pinfunction "1_1") (pintype "passive"))
      (node (ref "C4") (pin "1") (pinfunction "1_1") (pintype "passive"))
      (node (ref "C5") (pin "1") (pinfunction "1_1") (pintype "passive"))
      (node (ref "C6") (pin "1") (pinfunction "1_1") (pintype "passive"))
      (node (ref "C7") (pin "1") (pinfunction "1_1") (pintype "passive"))
      (node (ref "C8") (pin "1") (pinfunction "1_1") (pintype "passive"))
      (node (ref "C9") (pin "-") (pinfunction "-_-") (pintype "passive"))
      (node (ref "J1") (pin "P$1") (pinfunction "P$1_P$1") (pintype "bidirectional"))
      (node (ref "J2") (pin "P$1") (pinfunction "P$1_P$1") (pintype "bidirectional"))
      (node (ref "J3") (pin "3") (pinfunction "3_3") (pintype "passive"))
      (node (ref "J4") (pin "1") (pinfunction "1_1") (pintype "passive"))
      (node (ref "J4") (pin "20") (pinfunction "20_20") (pintype "passive"))
      (node (ref "J7") (pin "22") (pinfunction "22_22") (pintype "passive"))
      (node (ref "J8") (pin "1") (pinfunction "1_1") (pintype "passive"))
      (node (ref "J9") (pin "1") (pinfunction "1_1") (pintype "passive"))
      (node (ref "JP1") (pin "1") (pinfunction "1_1") (pintype "passive"))
      (node (ref "JP1") (pin "2") (pinfunction "2_2") (pintype "passive"))
      (node (ref "JP3") (pin "7") (pinfunction "7_7") (pintype "passive"))
      (node (ref "R1") (pin "2") (pinfunction "2_2") (pintype "passive"))
      (node (ref "R2") (pin "2") (pinfunction "2_2") (pintype "passive"))
      (node (ref "U2") (pin "1") (pinfunction "GND_1") (pintype "power_in"))
      (node (ref "U2") (pin "24") (pinfunction "~{A9}_24") (pintype "bidirectional"))
      (node (ref "U3") (pin "14") (pinfunction "GND_14") (pintype "power_in"))
      (node (ref "U4") (pin "10") (pinfunction "GND_10") (pintype "power_in"))
      (node (ref "U4") (pin "11") (pinfunction "OE_11") (pintype "input"))
      (node (ref "U6") (pin "10") (pinfunction "GND_10") (pintype "power_in"))
      (node (ref "U7") (pin "1") (pinfunction "G_1") (pintype "input"))
      (node (ref "U7") (pin "19") (pinfunction "G_19") (pintype "input"))
      (node (ref "U8") (pin "1") (pinfunction "G_1") (pintype "input"))
      (node (ref "U8") (pin "19") (pinfunction "G_19") (pintype "input"))
      (node (ref "U9") (pin "1") (pinfunction "GND_1") (pintype "power_in"))
      (node (ref "XC1") (pin "P$34") (pinfunction "X34_P$34") (pintype "bidirectional"))
      (node (ref "XC1") (pin "P$44") (pinfunction "X44_P$44") (pintype "bidirectional"))
    )
    (net (code "72") (name "IN-A00") (class "Default")
      (node (ref "U7") (pin "17") (pinfunction "A4_17") (pintype "input"))
      (node (ref "XC1") (pin "P$23") (pinfunction "X23_P$23") (pintype "bidirectional"))
    )
    (net (code "73") (name "IN-A01") (class "Default")
      (node (ref "U7") (pin "4") (pinfunction "A2_4") (pintype "input"))
      (node (ref "XC1") (pin "P$21") (pinfunction "X21_P$21") (pintype "bidirectional"))
    )
    (net (code "74") (name "IN-A02") (class "Default")
      (node (ref "U7") (pin "15") (pinfunction "A3_15") (pintype "input"))
      (node (ref "XC1") (pin "P$19") (pinfunction "X19_P$19") (pintype "bidirectional"))
    )
    (net (code "75") (name "IN-A03") (class "Default")
      (node (ref "U7") (pin "6") (pinfunction "A3_6") (pintype "input"))
      (node (ref "XC1") (pin "P$17") (pinfunction "X17_P$17") (pintype "bidirectional"))
    )
    (net (code "76") (name "IN-A04") (class "Default")
      (node (ref "U7") (pin "13") (pinfunction "A2_13") (pintype "input"))
      (node (ref "XC1") (pin "P$15") (pinfunction "X15_P$15") (pintype "bidirectional"))
    )
    (net (code "77") (name "IN-A05") (class "Default")
      (node (ref "U7") (pin "8") (pinfunction "A4_8") (pintype "input"))
      (node (ref "XC1") (pin "P$13") (pinfunction "X13_P$13") (pintype "bidirectional"))
    )
    (net (code "78") (name "IN-A06") (class "Default")
      (node (ref "U8") (pin "8") (pinfunction "A4_8") (pintype "input"))
      (node (ref "XC1") (pin "P$12") (pinfunction "X12_P$12") (pintype "bidirectional"))
    )
    (net (code "79") (name "IN-A07") (class "Default")
      (node (ref "U8") (pin "13") (pinfunction "A2_13") (pintype "input"))
      (node (ref "XC1") (pin "P$14") (pinfunction "X14_P$14") (pintype "bidirectional"))
    )
    (net (code "80") (name "IN-A08") (class "Default")
      (node (ref "U8") (pin "6") (pinfunction "A3_6") (pintype "input"))
      (node (ref "XC1") (pin "P$16") (pinfunction "X16_P$16") (pintype "bidirectional"))
    )
    (net (code "81") (name "IN-A09") (class "Default")
      (node (ref "U8") (pin "15") (pinfunction "A3_15") (pintype "input"))
      (node (ref "XC1") (pin "P$18") (pinfunction "X18_P$18") (pintype "bidirectional"))
    )
    (net (code "82") (name "IN-A10") (class "Default")
      (node (ref "U8") (pin "4") (pinfunction "A2_4") (pintype "input"))
      (node (ref "XC1") (pin "P$20") (pinfunction "X20_P$20") (pintype "bidirectional"))
    )
    (net (code "83") (name "IN-A11") (class "Default")
      (node (ref "U8") (pin "17") (pinfunction "A4_17") (pintype "input"))
      (node (ref "XC1") (pin "P$22") (pinfunction "X22_P$22") (pintype "bidirectional"))
    )
    (net (code "84") (name "IN-A12") (class "Default")
      (node (ref "U8") (pin "2") (pinfunction "A1_2") (pintype "input"))
      (node (ref "XC1") (pin "P$24") (pinfunction "X24_P$24") (pintype "bidirectional"))
    )
    (net (code "85") (name "IN-A13") (class "Default")
      (node (ref "U7") (pin "2") (pinfunction "A1_2") (pintype "input"))
      (node (ref "XC1") (pin "P$36") (pinfunction "X36_P$36") (pintype "bidirectional"))
    )
    (net (code "86") (name "IN-A14") (class "Default")
      (node (ref "U8") (pin "11") (pinfunction "A1_11") (pintype "input"))
      (node (ref "XC1") (pin "P$10") (pinfunction "X10_P$10") (pintype "bidirectional"))
    )
    (net (code "87") (name "IN-A15") (class "Default")
      (node (ref "U7") (pin "11") (pinfunction "A1_11") (pintype "input"))
      (node (ref "XC1") (pin "P$9") (pinfunction "X9_P$9") (pintype "bidirectional"))
    )
    (net (code "88") (name "Net-(Q1-PadB)") (class "Default")
      (node (ref "Q1") (pin "B") (pinfunction "B_B") (pintype "passive"))
      (node (ref "R1") (pin "1") (pinfunction "1_1") (pintype "passive"))
      (node (ref "R3") (pin "1") (pinfunction "1_1") (pintype "passive"))
    )
    (net (code "89") (name "Net-(Q1-PadC)") (class "Default")
      (node (ref "Q1") (pin "C") (pinfunction "C_C") (pintype "passive"))
      (node (ref "SJ4") (pin "2") (pinfunction "2_2") (pintype "passive"))
    )
    (net (code "90") (name "Net-(U1A-A5)") (class "Default")
      (node (ref "J5") (pin "2") (pinfunction "2_2") (pintype "passive"))
      (node (ref "U1") (pin "1") (pinfunction "A5_1") (pintype "input"))
    )
    (net (code "91") (name "Net-(U2-CLK)") (class "Default")
      (node (ref "U2") (pin "22") (pinfunction "CLK_22") (pintype "input"))
      (node (ref "U5") (pin "5") (pinfunction "Q_5") (pintype "output"))
    )
    (net (code "92") (name "Net-(U3-A14)") (class "Default")
      (node (ref "J8") (pin "2") (pinfunction "2_2") (pintype "passive"))
      (node (ref "U3") (pin "27") (pinfunction "A14_27") (pintype "input"))
    )
    (net (code "93") (name "Net-(U3-A15)") (class "Default")
      (node (ref "J9") (pin "2") (pinfunction "2_2") (pintype "passive"))
      (node (ref "U3") (pin "1") (pinfunction "A15_1") (pintype "input"))
    )
    (net (code "94") (name "Net-(U5A-D)") (class "Default")
      (node (ref "U5") (pin "2") (pinfunction "D_2") (pintype "input"))
      (node (ref "U5") (pin "6") (pinfunction "~{Q}_6") (pintype "output"))
    )
    (net (code "95") (name "Net-(U6-OE)") (class "Default")
      (node (ref "J3") (pin "2") (pinfunction "2_2") (pintype "passive"))
      (node (ref "U6") (pin "11") (pinfunction "OE_11") (pintype "input"))
    )
    (net (code "96") (name "R-SP01") (class "Default")
      (node (ref "J6") (pin "9") (pinfunction "9_9") (pintype "passive"))
      (node (ref "U6") (pin "18") (pinfunction "O2_18") (pintype "output"))
    )
    (net (code "97") (name "RAM-A14") (class "Default")
      (node (ref "U1") (pin "10") (pinfunction "A14_10") (pintype "input"))
      (node (ref "U6") (pin "19") (pinfunction "O1_19") (pintype "output"))
    )
    (net (code "98") (name "SND") (class "Default")
      (node (ref "J6") (pin "21") (pinfunction "21_21") (pintype "passive"))
      (node (ref "SJ4") (pin "1") (pinfunction "1_1") (pintype "passive"))
      (node (ref "XC1") (pin "P$2") (pinfunction "X2_P$2") (pintype "bidirectional"))
    )
    (net (code "99") (name "VCC") (class "Default")
      (node (ref "C1") (pin "2") (pinfunction "2_2") (pintype "passive"))
      (node (ref "C2") (pin "1") (pinfunction "1_1") (pintype "passive"))
      (node (ref "C3") (pin "2") (pinfunction "2_2") (pintype "passive"))
      (node (ref "C4") (pin "2") (pinfunction "2_2") (pintype "passive"))
      (node (ref "C5") (pin "2") (pinfunction "2_2") (pintype "passive"))
      (node (ref "C6") (pin "2") (pinfunction "2_2") (pintype "passive"))
      (node (ref "C7") (pin "2") (pinfunction "2_2") (pintype "passive"))
      (node (ref "C8") (pin "2") (pinfunction "2_2") (pintype "passive"))
      (node (ref "C9") (pin "+") (pinfunction "+_+") (pintype "passive"))
      (node (ref "J3") (pin "1") (pinfunction "1_1") (pintype "passive"))
      (node (ref "J4") (pin "10") (pinfunction "10_10") (pintype "passive"))
      (node (ref "J4") (pin "11") (pinfunction "11_11") (pintype "passive"))
      (node (ref "J5") (pin "1") (pinfunction "1_1") (pintype "passive"))
      (node (ref "J6") (pin "22") (pinfunction "22_22") (pintype "passive"))
      (node (ref "J8") (pin "3") (pinfunction "3_3") (pintype "passive"))
      (node (ref "J9") (pin "3") (pinfunction "3_3") (pintype "passive"))
      (node (ref "JP1") (pin "3") (pinfunction "3_3") (pintype "passive"))
      (node (ref "JP3") (pin "8") (pinfunction "8_8") (pintype "passive"))
      (node (ref "R3") (pin "2") (pinfunction "2_2") (pintype "passive"))
      (node (ref "U2") (pin "25") (pinfunction "A8_25") (pintype "bidirectional"))
      (node (ref "U2") (pin "28") (pinfunction "BC2_28") (pintype "bidirectional"))
      (node (ref "U2") (pin "40") (pinfunction "VCC_40") (pintype "power_in"))
      (node (ref "U3") (pin "28") (pinfunction "VCC_28") (pintype "power_in"))
      (node (ref "U4") (pin "20") (pinfunction "VCC_20") (pintype "power_in"))
      (node (ref "U5") (pin "1") (pinfunction "CLR_1") (pintype "input"))
      (node (ref "U5") (pin "4") (pinfunction "PRE_4") (pintype "input"))
      (node (ref "U6") (pin "20") (pinfunction "VCC_20") (pintype "power_in"))
      (node (ref "U9") (pin "3") (pinfunction "VCC_3") (pintype "power_in"))
      (node (ref "XC1") (pin "P$25") (pinfunction "X25_P$25") (pintype "bidirectional"))
    )
    (net (code "100") (name "unconnected-(JP3-Pad4)") (class "Default")
      (node (ref "JP3") (pin "4") (pinfunction "4_4") (pintype "passive"))
    )
    (net (code "101") (name "unconnected-(U2-TST1-Pad39)") (class "Default")
      (node (ref "U2") (pin "39") (pinfunction "TST1_39") (pintype "bidirectional"))
    )
    (net (code "102") (name "unconnected-(U2-TST2-Pad26)") (class "Default")
      (node (ref "U2") (pin "26") (pinfunction "TST2_26") (pintype "bidirectional"))
    )
    (net (code "103") (name "unconnected-(U5B-CLK-Pad11)") (class "Default")
      (node (ref "U5") (pin "11") (pinfunction "CLK_11") (pintype "input"))
    )
    (net (code "104") (name "unconnected-(U5B-CLR-Pad13)") (class "Default")
      (node (ref "U5") (pin "13") (pinfunction "CLR_13") (pintype "input"))
    )
    (net (code "105") (name "unconnected-(U5B-D-Pad12)") (class "Default")
      (node (ref "U5") (pin "12") (pinfunction "D_12") (pintype "input"))
    )
    (net (code "106") (name "unconnected-(U5B-PRE-Pad10)") (class "Default")
      (node (ref "U5") (pin "10") (pinfunction "PRE_10") (pintype "input"))
    )
    (net (code "107") (name "unconnected-(U5B-Q-Pad9)") (class "Default")
      (node (ref "U5") (pin "9") (pinfunction "Q_9") (pintype "output"))
    )
    (net (code "108") (name "unconnected-(U5B-~{Q}-Pad8)") (class "Default")
      (node (ref "U5") (pin "8") (pinfunction "~{Q}_8") (pintype "output"))
    )
    (net (code "109") (name "Φ") (class "Default")
      (node (ref "J6") (pin "14") (pinfunction "14_14") (pintype "passive"))
      (node (ref "U5") (pin "3") (pinfunction "CLK_3") (pintype "input"))
      (node (ref "XC1") (pin "P$8") (pinfunction "X8_P$8") (pintype "bidirectional"))
    )
  )
)
